# eNode_Spark.net
KiCad netlist of a schematic drawn in EAGLE
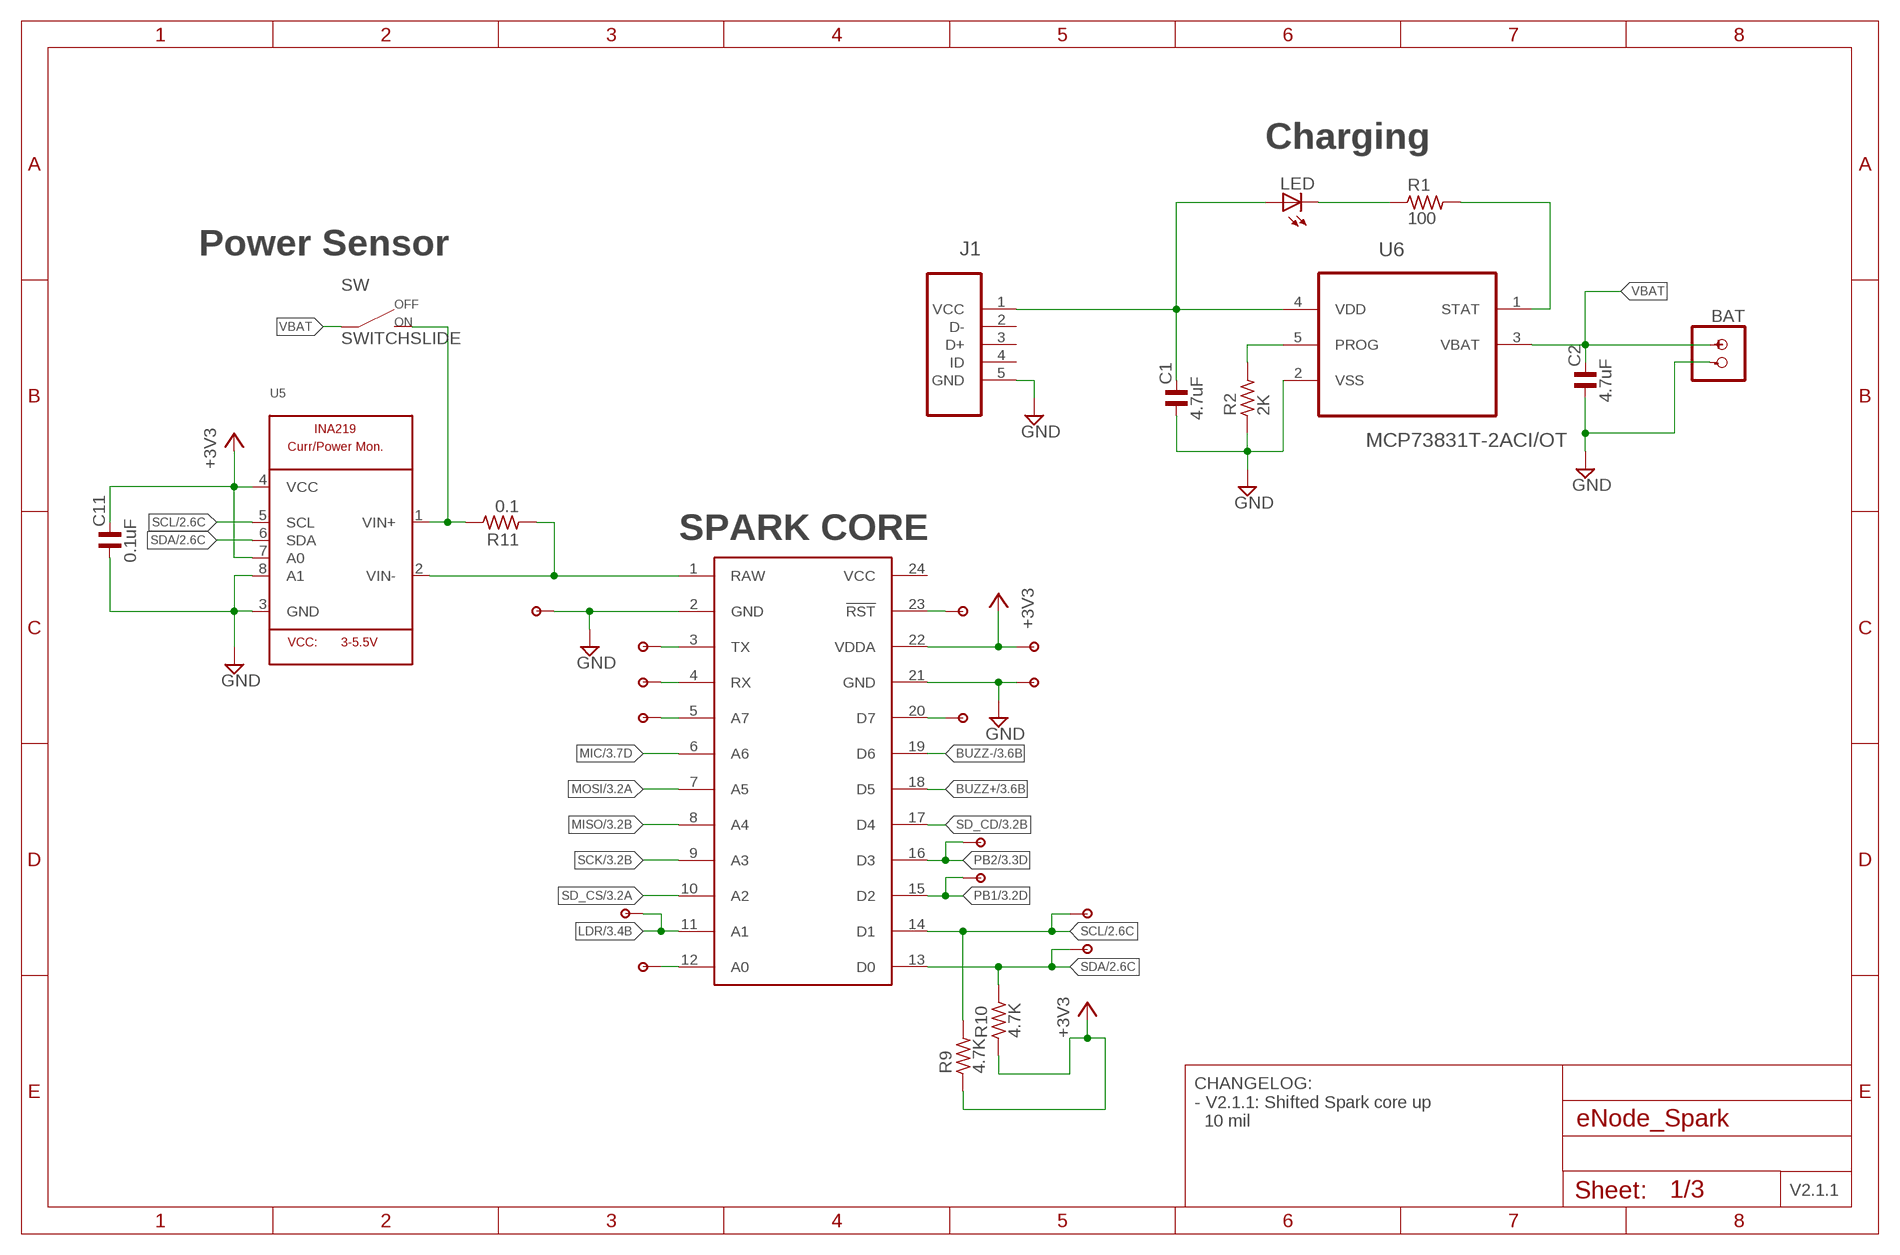
[diagram p0: schematic, sheet 1]
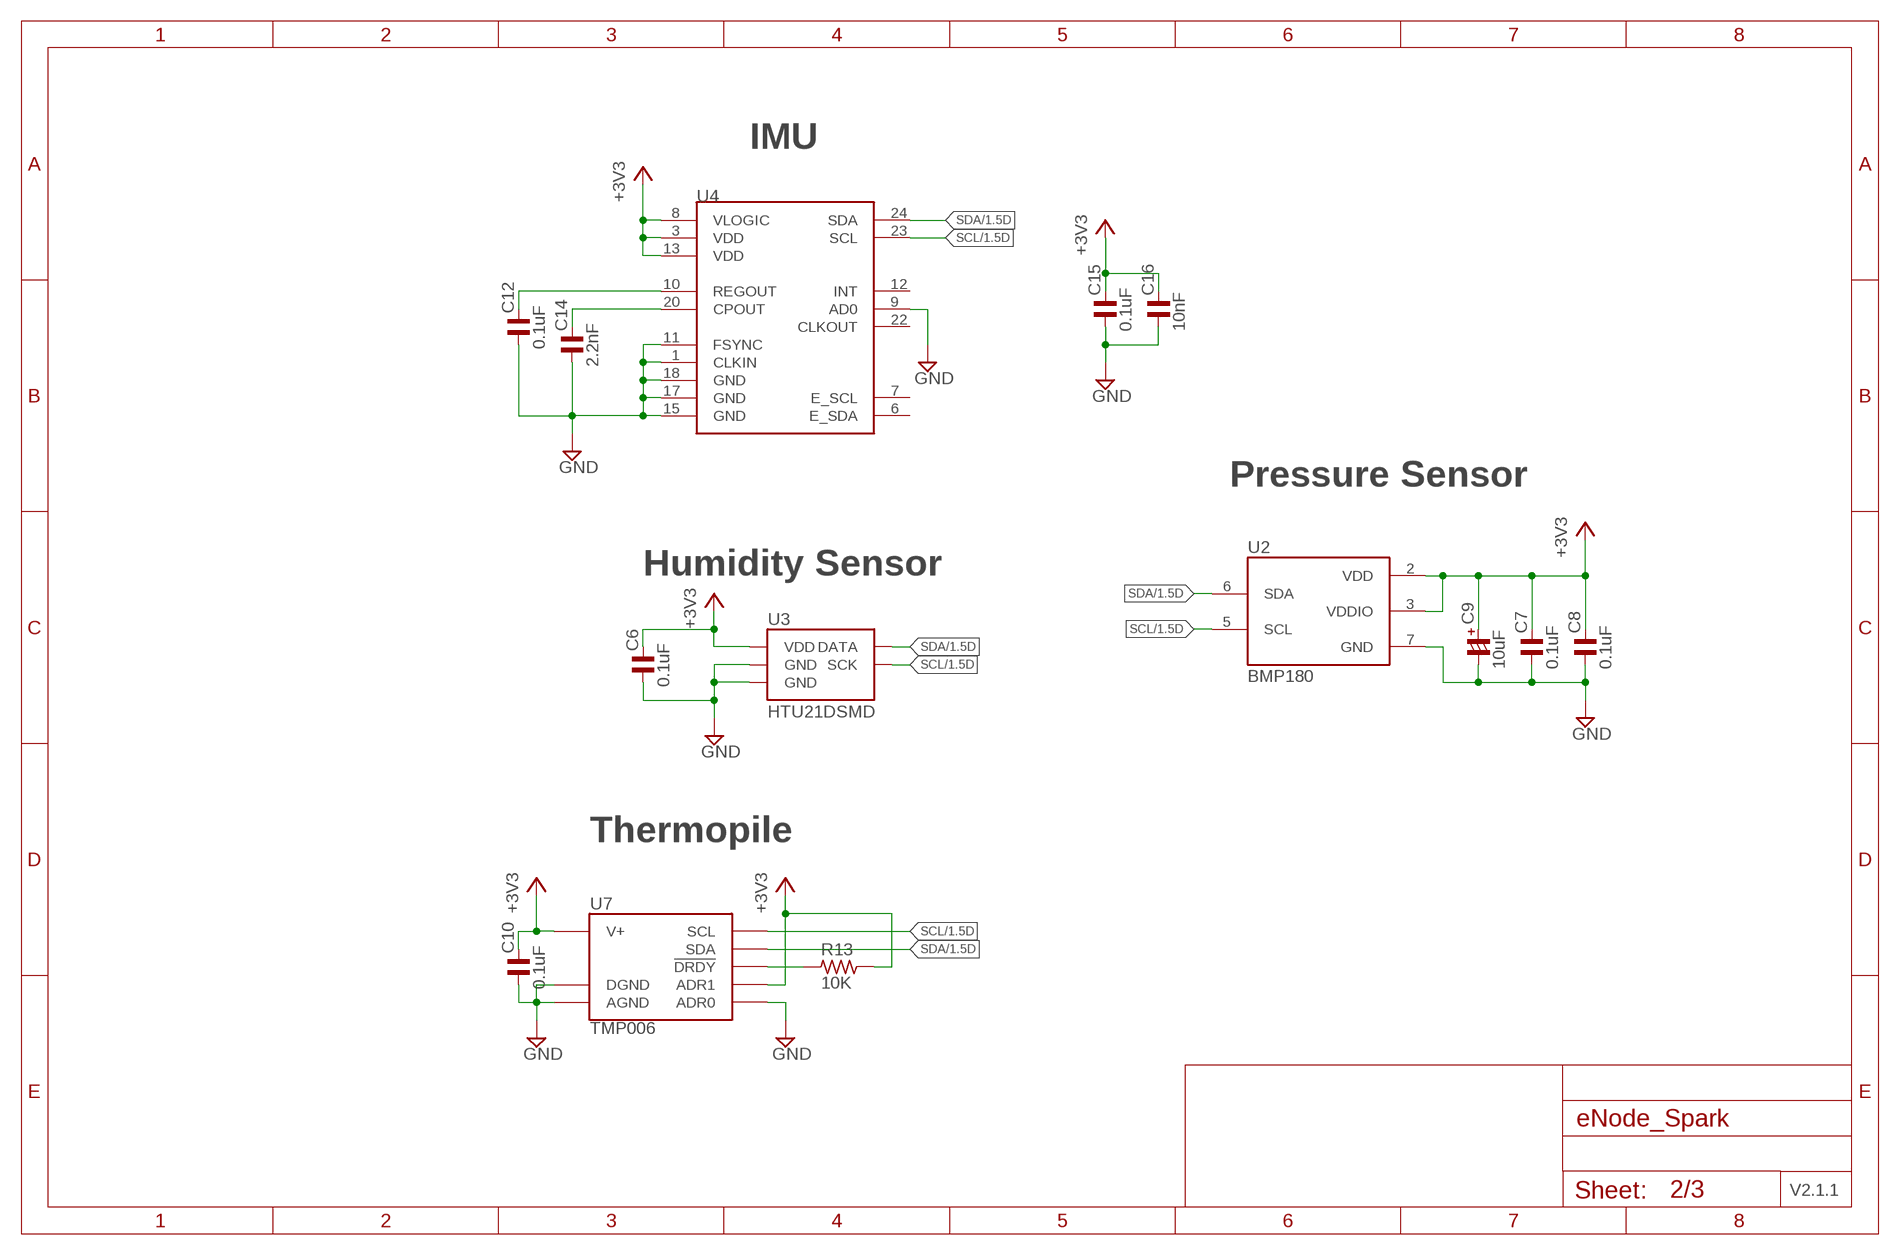
[diagram p1: schematic, sheet 2]
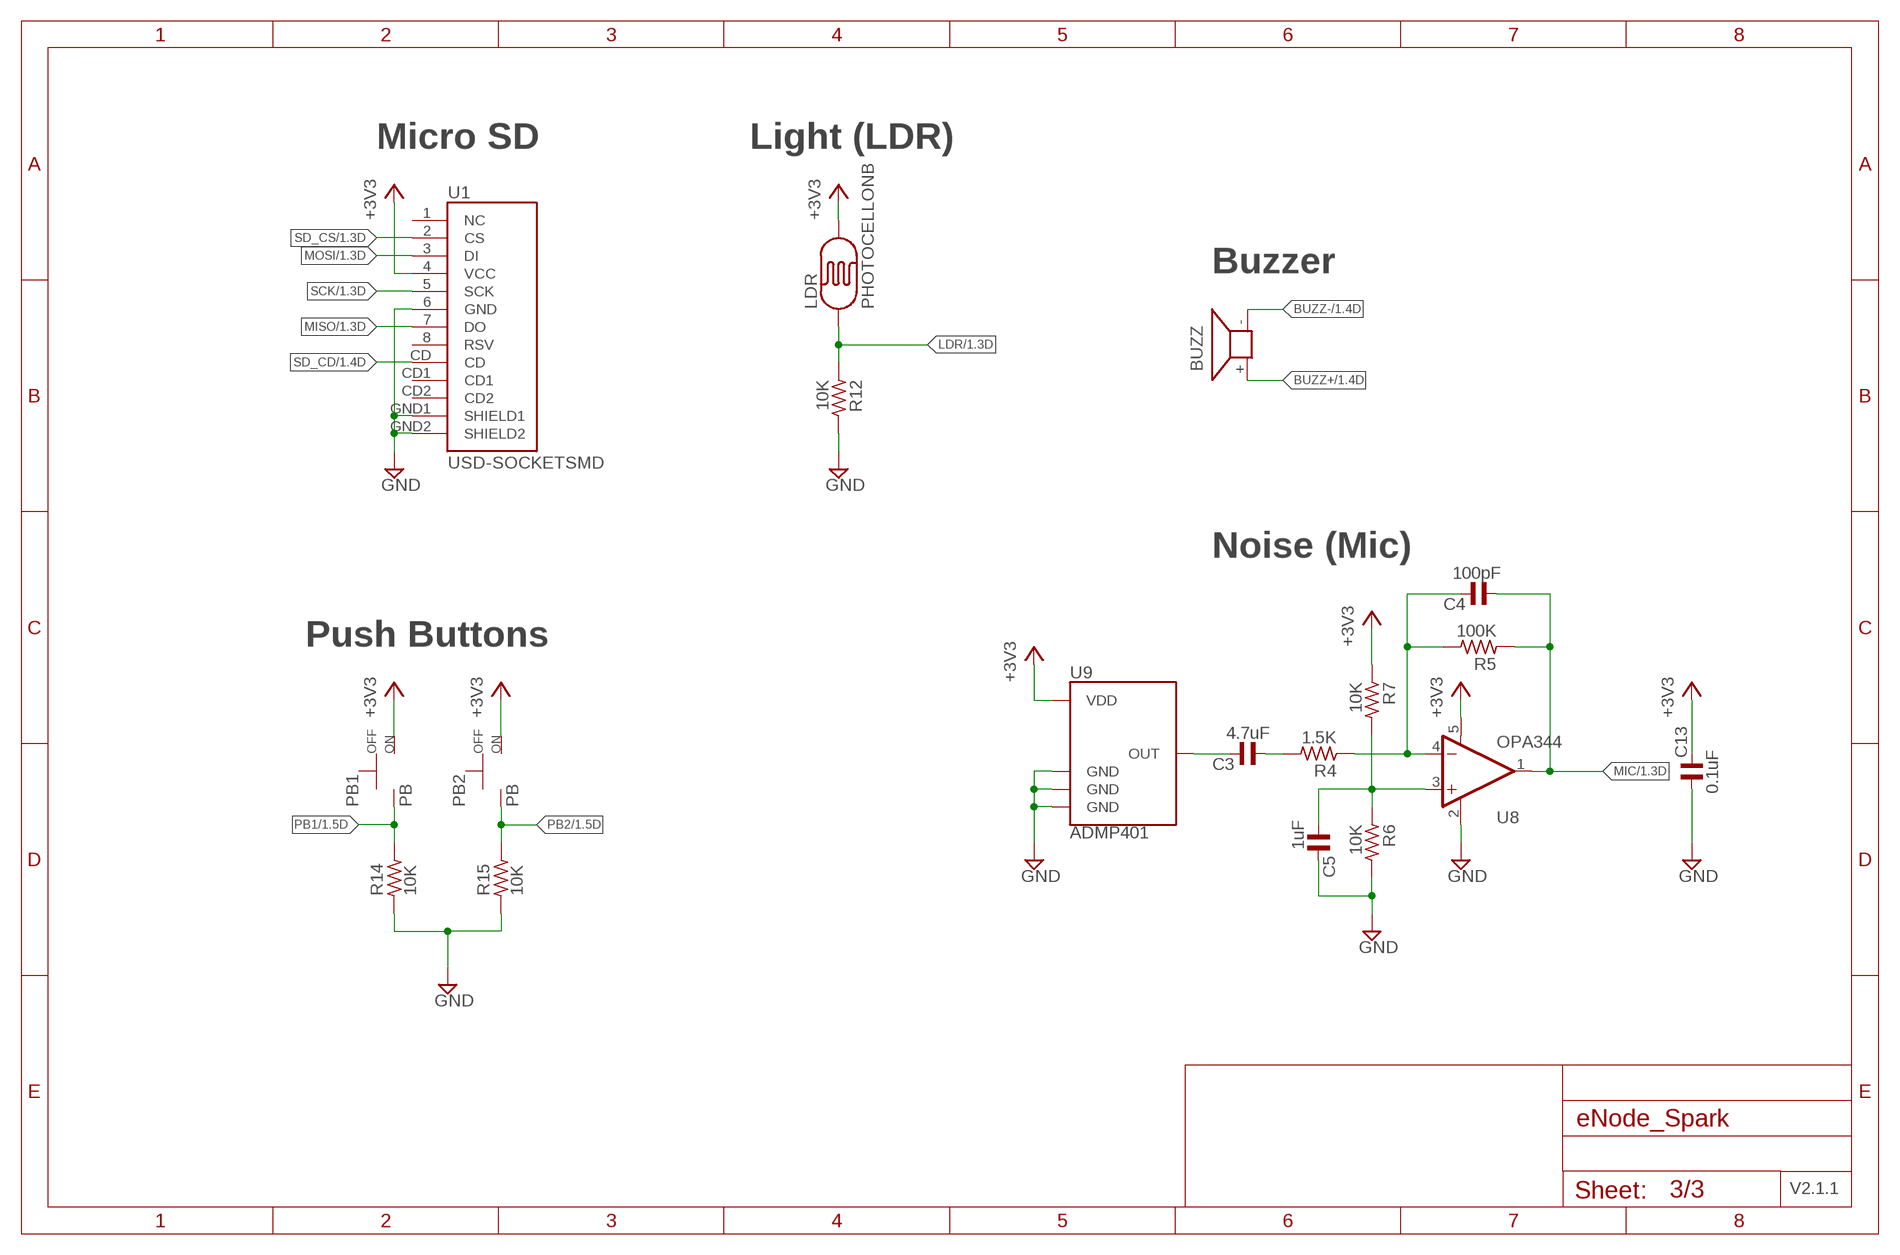
[diagram p2: schematic, sheet 3]

(export (version "E")
  (design (tool "Eeschema 10.0.6"))
  (components
    (comp (ref "BAT")
      (value "BATTERYSMT")
      (footprint "eagle-import:JST-2-SMD")
      (libsource (lib "eagle-import") (part "BATTERYSMT"))
    )
    (comp (ref "C1")
      (value "4.7uF")
      (footprint "eagle-import:C0402")
      (libsource (lib "eagle-import") (part "C_0402"))
    )
    (comp (ref "C2")
      (value "4.7uF")
      (footprint "eagle-import:C0402")
      (libsource (lib "eagle-import") (part "C_0402"))
    )
    (comp (ref "C11")
      (value "0.1uF")
      (footprint "eagle-import:C0402")
      (libsource (lib "eagle-import") (part "C_0402"))
    )
    (comp (ref "J1")
      (value "47346-0001")
      (footprint "eagle-import:MOLEX_47346-0001")
      (libsource (lib "eagle-import") (part "47346-0001"))
    )
    (comp (ref "LED")
      (value "LED")
      (footprint "eagle-import:RA_SMD_LED")
      (libsource (lib "eagle-import") (part "LED"))
    )
    (comp (ref "R1")
      (value "100")
      (footprint "eagle-import:R0603")
      (libsource (lib "eagle-import") (part "R_0603"))
    )
    (comp (ref "R2")
      (value "2K")
      (footprint "eagle-import:R0603")
      (libsource (lib "eagle-import") (part "R_0603"))
    )
    (comp (ref "R9")
      (value "4.7K")
      (footprint "eagle-import:R0603")
      (libsource (lib "eagle-import") (part "R_0603"))
    )
    (comp (ref "R10")
      (value "4.7K")
      (footprint "eagle-import:R0603")
      (libsource (lib "eagle-import") (part "R_0603"))
    )
    (comp (ref "R11")
      (value "0.1")
      (footprint "eagle-import:R2512")
      (libsource (lib "eagle-import") (part "R_2512"))
    )
    (comp (ref "SPARK")
      (value "SPARK_CORECORE")
      (footprint "eagle-import:SPARK_CORE")
      (libsource (lib "eagle-import") (part "SPARK_CORECORE"))
    )
    (comp (ref "SW")
      (value "SWITCHSLIDE")
      (footprint "eagle-import:CHANGE_OVER_SLIDE")
      (libsource (lib "eagle-import") (part "SWITCHSLIDE"))
    )
    (comp (ref "U$1")
      (value "1PIN")
      (footprint "eagle-import:1PIN")
      (libsource (lib "eagle-import") (part "1PIN"))
    )
    (comp (ref "U$2")
      (value "1PIN")
      (footprint "eagle-import:1PIN")
      (libsource (lib "eagle-import") (part "1PIN"))
    )
    (comp (ref "U$6")
      (value "1PIN")
      (footprint "eagle-import:1PIN")
      (libsource (lib "eagle-import") (part "1PIN"))
    )
    (comp (ref "U$7")
      (value "1PIN")
      (footprint "eagle-import:1PIN")
      (libsource (lib "eagle-import") (part "1PIN"))
    )
    (comp (ref "U$8")
      (value "1PIN")
      (footprint "eagle-import:1PIN")
      (libsource (lib "eagle-import") (part "1PIN"))
    )
    (comp (ref "U$9")
      (value "1PIN")
      (footprint "eagle-import:1PIN")
      (libsource (lib "eagle-import") (part "1PIN"))
    )
    (comp (ref "U$10")
      (value "1PIN")
      (footprint "eagle-import:1PIN")
      (libsource (lib "eagle-import") (part "1PIN"))
    )
    (comp (ref "U$11")
      (value "1PIN")
      (footprint "eagle-import:1PIN")
      (libsource (lib "eagle-import") (part "1PIN"))
    )
    (comp (ref "U$12")
      (value "1PIN")
      (footprint "eagle-import:1PIN")
      (libsource (lib "eagle-import") (part "1PIN"))
    )
    (comp (ref "U$13")
      (value "1PIN")
      (footprint "eagle-import:1PIN")
      (libsource (lib "eagle-import") (part "1PIN"))
    )
    (comp (ref "U$14")
      (value "1PIN")
      (footprint "eagle-import:1PIN")
      (libsource (lib "eagle-import") (part "1PIN"))
    )
    (comp (ref "U$15")
      (value "1PIN")
      (footprint "eagle-import:1PIN")
      (libsource (lib "eagle-import") (part "1PIN"))
    )
    (comp (ref "U$16")
      (value "1PIN")
      (footprint "eagle-import:1PIN")
      (libsource (lib "eagle-import") (part "1PIN"))
    )
    (comp (ref "U$17")
      (value "1PIN")
      (footprint "eagle-import:1PIN")
      (libsource (lib "eagle-import") (part "1PIN"))
    )
    (comp (ref "U5")
      (value "INA219")
      (footprint "eagle-import:SOT23-8")
      (libsource (lib "eagle-import") (part "INA219"))
    )
    (comp (ref "U6")
      (value "MCP73831T-2ACI/OT")
      (footprint "eagle-import:SOT95P280X145-5N")
      (libsource (lib "eagle-import") (part "MCP73831T-2ACI/OT"))
    )
    (comp (ref "C6")
      (value "0.1uF")
      (footprint "eagle-import:C0402")
      (libsource (lib "eagle-import") (part "C_0402"))
    )
    (comp (ref "C7")
      (value "0.1uF")
      (footprint "eagle-import:C0402")
      (libsource (lib "eagle-import") (part "C_0402"))
    )
    (comp (ref "C8")
      (value "0.1uF")
      (footprint "eagle-import:C0402")
      (libsource (lib "eagle-import") (part "C_0402"))
    )
    (comp (ref "C9")
      (value "10uF")
      (footprint "eagle-import:C1206_T")
      (libsource (lib "eagle-import") (part "CP_1206/T"))
    )
    (comp (ref "C10")
      (value "0.1uF")
      (footprint "eagle-import:C0402")
      (libsource (lib "eagle-import") (part "C_0402"))
    )
    (comp (ref "C12")
      (value "0.1uF")
      (footprint "eagle-import:C0402")
      (libsource (lib "eagle-import") (part "C_0402"))
    )
    (comp (ref "C14")
      (value "2.2nF")
      (footprint "eagle-import:C0402")
      (libsource (lib "eagle-import") (part "C_0402"))
    )
    (comp (ref "C15")
      (value "0.1uF")
      (footprint "eagle-import:C0402")
      (libsource (lib "eagle-import") (part "C_0402"))
    )
    (comp (ref "C16")
      (value "10nF")
      (footprint "eagle-import:C0402")
      (libsource (lib "eagle-import") (part "C_0402"))
    )
    (comp (ref "R13")
      (value "10K")
      (footprint "eagle-import:R0603")
      (libsource (lib "eagle-import") (part "R_0603"))
    )
    (comp (ref "U2")
      (value "BMP180")
      (footprint "eagle-import:BMP180")
      (libsource (lib "eagle-import") (part "BMP180"))
    )
    (comp (ref "U3")
      (value "HTU21DSMD")
      (footprint "eagle-import:HTU21D")
      (libsource (lib "eagle-import") (part "HTU21DSMD"))
    )
    (comp (ref "U4")
      (value "MPU-9150QFN-24-NP")
      (footprint "eagle-import:QFN-24-NP")
      (libsource (lib "eagle-import") (part "MPU-9150QFN-24-NP"))
    )
    (comp (ref "U7")
      (value "TMP006")
      (footprint "eagle-import:BGA8DS")
      (libsource (lib "eagle-import") (part "TMP006"))
    )
    (comp (ref "BUZZ")
      (value "BUZZER")
      (footprint "eagle-import:OFFBOARD_NOSIGN")
      (libsource (lib "eagle-import") (part "BUZZER"))
    )
    (comp (ref "C3")
      (value "4.7uF")
      (footprint "eagle-import:C0402")
      (libsource (lib "eagle-import") (part "C_0402"))
    )
    (comp (ref "C4")
      (value "100pF")
      (footprint "eagle-import:C0402")
      (libsource (lib "eagle-import") (part "C_0402"))
    )
    (comp (ref "C5")
      (value "1uF")
      (footprint "eagle-import:C0402")
      (libsource (lib "eagle-import") (part "C_0402"))
    )
    (comp (ref "C13")
      (value "0.1uF")
      (footprint "eagle-import:C0402")
      (libsource (lib "eagle-import") (part "C_0402"))
    )
    (comp (ref "LDR")
      (value "PHOTOCELLONB")
      (footprint "eagle-import:ON_BOARD")
      (libsource (lib "eagle-import") (part "PHOTOCELLONB"))
    )
    (comp (ref "PB1") (value "PB") (footprint "eagle-import:PB") (libsource (lib "eagle-import") (part "PB")))
    (comp (ref "PB2") (value "PB") (footprint "eagle-import:PB") (libsource (lib "eagle-import") (part "PB")))
    (comp (ref "R4")
      (value "1.5K")
      (footprint "eagle-import:R0402")
      (libsource (lib "eagle-import") (part "R_0402"))
    )
    (comp (ref "R5")
      (value "100K")
      (footprint "eagle-import:R0402")
      (libsource (lib "eagle-import") (part "R_0402"))
    )
    (comp (ref "R6")
      (value "10K")
      (footprint "eagle-import:R0402")
      (libsource (lib "eagle-import") (part "R_0402"))
    )
    (comp (ref "R7")
      (value "10K")
      (footprint "eagle-import:R0402")
      (libsource (lib "eagle-import") (part "R_0402"))
    )
    (comp (ref "R12")
      (value "10K")
      (footprint "eagle-import:R0603")
      (libsource (lib "eagle-import") (part "R_0603"))
    )
    (comp (ref "R14")
      (value "10K")
      (footprint "eagle-import:R0603")
      (libsource (lib "eagle-import") (part "R_0603"))
    )
    (comp (ref "R15")
      (value "10K")
      (footprint "eagle-import:R0603")
      (libsource (lib "eagle-import") (part "R_0603"))
    )
    (comp (ref "U1")
      (value "USD-SOCKETSMD")
      (footprint "eagle-import:MICRO-SD-SOCKET-PP")
      (libsource (lib "eagle-import") (part "USD-SOCKETSMD"))
    )
    (comp (ref "U8")
      (value "OPA344")
      (footprint "eagle-import:SOT23-5")
      (libsource (lib "eagle-import") (part "OPA344"))
    )
    (comp (ref "U9")
      (value "ADMP401")
      (footprint "eagle-import:ADMP401")
      (libsource (lib "eagle-import") (part "ADMP401"))
    )
  )
  (nets
    (net (code "1") (name "+3V3") (class "Default")
      (node (ref "C10") (pin "2") (pinfunction "2_2") (pintype "passive"))
      (node (ref "C11") (pin "2") (pinfunction "2_2") (pintype "passive"))
      (node (ref "C13") (pin "2") (pinfunction "2_2") (pintype "passive"))
      (node (ref "C15") (pin "2") (pinfunction "2_2") (pintype "passive"))
      (node (ref "C16") (pin "2") (pinfunction "2_2") (pintype "passive"))
      (node (ref "C6") (pin "2") (pinfunction "2_2") (pintype "passive"))
      (node (ref "C7") (pin "2") (pinfunction "2_2") (pintype "passive"))
      (node (ref "C8") (pin "2") (pinfunction "2_2") (pintype "passive"))
      (node (ref "C9") (pin "+") (pinfunction "+_+") (pintype "passive"))
      (node (ref "LDR") (pin "2") (pinfunction "P$2_2") (pintype "bidirectional"))
      (node (ref "PB1") (pin "2") (pinfunction "2_2") (pintype "bidirectional"))
      (node (ref "PB2") (pin "2") (pinfunction "2_2") (pintype "bidirectional"))
      (node (ref "R10") (pin "1") (pinfunction "1_1") (pintype "passive"))
      (node (ref "R13") (pin "2") (pinfunction "2_2") (pintype "passive"))
      (node (ref "R7") (pin "1") (pinfunction "1_1") (pintype "passive"))
      (node (ref "R9") (pin "1") (pinfunction "1_1") (pintype "passive"))
      (node (ref "SPARK") (pin "22") (pinfunction "VDDA_22") (pintype "power_in"))
      (node (ref "U$6") (pin "P$1") (pinfunction "P$1_P$1") (pintype "bidirectional"))
      (node (ref "U1") (pin "4") (pinfunction "VCC_4") (pintype "bidirectional"))
      (node (ref "U2") (pin "2") (pinfunction "VDD_2") (pintype "power_in"))
      (node (ref "U2") (pin "3") (pinfunction "VDDIO_3") (pintype "power_in"))
      (node (ref "U3") (pin "VDD") (pinfunction "VDD_VDD") (pintype "power_in"))
      (node (ref "U4") (pin "13") (pinfunction "VDD_13") (pintype "bidirectional"))
      (node (ref "U4") (pin "3") (pinfunction "VDD_3") (pintype "bidirectional"))
      (node (ref "U4") (pin "8") (pinfunction "VLOGIC_8") (pintype "bidirectional"))
      (node (ref "U5") (pin "4") (pinfunction "VCC_4") (pintype "bidirectional"))
      (node (ref "U5") (pin "7") (pinfunction "A0_7") (pintype "bidirectional"))
      (node (ref "U7") (pin "A3") (pinfunction "V+_A3") (pintype "bidirectional"))
      (node (ref "U7") (pin "B1") (pinfunction "ADR1_B1") (pintype "bidirectional"))
      (node (ref "U8") (pin "5") (pinfunction "V+_5") (pintype "power_in"))
      (node (ref "U9") (pin "5") (pinfunction "VDD_5") (pintype "bidirectional"))
    )
    (net (code "2") (name "BUZZ+") (class "Default")
      (node (ref "BUZZ") (pin "+") (pinfunction "+_+") (pintype "passive"))
      (node (ref "SPARK") (pin "18") (pinfunction "D5_18") (pintype "bidirectional"))
    )
    (net (code "3") (name "BUZZ-") (class "Default")
      (node (ref "BUZZ") (pin "-") (pinfunction "-_-") (pintype "passive"))
      (node (ref "SPARK") (pin "19") (pinfunction "D6_19") (pintype "bidirectional"))
    )
    (net (code "4") (name "GND") (class "Default")
      (node (ref "BAT") (pin "-") (pinfunction "-_-") (pintype "passive"))
      (node (ref "C1") (pin "1") (pinfunction "1_1") (pintype "passive"))
      (node (ref "C10") (pin "1") (pinfunction "1_1") (pintype "passive"))
      (node (ref "C11") (pin "1") (pinfunction "1_1") (pintype "passive"))
      (node (ref "C12") (pin "1") (pinfunction "1_1") (pintype "passive"))
      (node (ref "C13") (pin "1") (pinfunction "1_1") (pintype "passive"))
      (node (ref "C14") (pin "1") (pinfunction "1_1") (pintype "passive"))
      (node (ref "C15") (pin "1") (pinfunction "1_1") (pintype "passive"))
      (node (ref "C16") (pin "1") (pinfunction "1_1") (pintype "passive"))
      (node (ref "C2") (pin "1") (pinfunction "1_1") (pintype "passive"))
      (node (ref "C5") (pin "2") (pinfunction "2_2") (pintype "passive"))
      (node (ref "C6") (pin "1") (pinfunction "1_1") (pintype "passive"))
      (node (ref "C7") (pin "1") (pinfunction "1_1") (pintype "passive"))
      (node (ref "C8") (pin "1") (pinfunction "1_1") (pintype "passive"))
      (node (ref "C9") (pin "-") (pinfunction "-_-") (pintype "passive"))
      (node (ref "J1") (pin "5") (pinfunction "GND_5") (pintype "input"))
      (node (ref "R12") (pin "2") (pinfunction "2_2") (pintype "passive"))
      (node (ref "R14") (pin "1") (pinfunction "1_1") (pintype "passive"))
      (node (ref "R15") (pin "1") (pinfunction "1_1") (pintype "passive"))
      (node (ref "R2") (pin "1") (pinfunction "1_1") (pintype "passive"))
      (node (ref "R6") (pin "2") (pinfunction "2_2") (pintype "passive"))
      (node (ref "SPARK") (pin "2") (pinfunction "GND_2") (pintype "power_in"))
      (node (ref "SPARK") (pin "21") (pinfunction "GND_21") (pintype "power_in"))
      (node (ref "U$11") (pin "P$1") (pinfunction "P$1_P$1") (pintype "bidirectional"))
      (node (ref "U$17") (pin "P$1") (pinfunction "P$1_P$1") (pintype "bidirectional"))
      (node (ref "U1") (pin "6") (pinfunction "GND_6") (pintype "bidirectional"))
      (node (ref "U1") (pin "GND1") (pinfunction "SHIELD1_GND1") (pintype "bidirectional"))
      (node (ref "U1") (pin "GND2") (pinfunction "SHIELD2_GND2") (pintype "bidirectional"))
      (node (ref "U2") (pin "7") (pinfunction "GND_7") (pintype "power_in"))
      (node (ref "U3") (pin "7") (pinfunction "GND_7") (pintype "power_in"))
      (node (ref "U3") (pin "GND") (pinfunction "GND_GND") (pintype "power_in"))
      (node (ref "U4") (pin "1") (pinfunction "CLKIN_1") (pintype "bidirectional"))
      (node (ref "U4") (pin "11") (pinfunction "FSYNC_11") (pintype "bidirectional"))
      (node (ref "U4") (pin "15") (pinfunction "GND_15") (pintype "bidirectional"))
      (node (ref "U4") (pin "17") (pinfunction "GND_17") (pintype "bidirectional"))
      (node (ref "U4") (pin "18") (pinfunction "GND_18") (pintype "bidirectional"))
      (node (ref "U4") (pin "9") (pinfunction "AD0_9") (pintype "bidirectional"))
      (node (ref "U5") (pin "3") (pinfunction "GND_3") (pintype "bidirectional"))
      (node (ref "U5") (pin "8") (pinfunction "A1_8") (pintype "bidirectional"))
      (node (ref "U6") (pin "2") (pinfunction "VSS_2") (pintype "power_in"))
      (node (ref "U7") (pin "A1") (pinfunction "DGND_A1") (pintype "bidirectional"))
      (node (ref "U7") (pin "A2") (pinfunction "AGND_A2") (pintype "bidirectional"))
      (node (ref "U7") (pin "C1") (pinfunction "ADR0_C1") (pintype "bidirectional"))
      (node (ref "U8") (pin "2") (pinfunction "V-_2") (pintype "power_in"))
      (node (ref "U9") (pin "2") (pinfunction "GND_2") (pintype "bidirectional"))
      (node (ref "U9") (pin "4") (pinfunction "GND_4") (pintype "bidirectional"))
      (node (ref "U9") (pin "6") (pinfunction "GND_6") (pintype "bidirectional"))
    )
    (net (code "5") (name "LDR") (class "Default")
      (node (ref "LDR") (pin "1") (pinfunction "P$1_1") (pintype "bidirectional"))
      (node (ref "R12") (pin "1") (pinfunction "1_1") (pintype "passive"))
      (node (ref "SPARK") (pin "11") (pinfunction "A1_11") (pintype "bidirectional"))
      (node (ref "U$16") (pin "P$1") (pinfunction "P$1_P$1") (pintype "bidirectional"))
    )
    (net (code "6") (name "MIC") (class "Default")
      (node (ref "C4") (pin "1") (pinfunction "1_1") (pintype "passive"))
      (node (ref "R5") (pin "1") (pinfunction "1_1") (pintype "passive"))
      (node (ref "SPARK") (pin "6") (pinfunction "A6_6") (pintype "bidirectional"))
      (node (ref "U8") (pin "1") (pinfunction "OUT_1") (pintype "output"))
    )
    (net (code "7") (name "MISO") (class "Default")
      (node (ref "SPARK") (pin "8") (pinfunction "A4_8") (pintype "bidirectional"))
      (node (ref "U1") (pin "7") (pinfunction "DO_7") (pintype "bidirectional"))
    )
    (net (code "8") (name "MOSI") (class "Default")
      (node (ref "SPARK") (pin "7") (pinfunction "A5_7") (pintype "bidirectional"))
      (node (ref "U1") (pin "3") (pinfunction "DI_3") (pintype "bidirectional"))
    )
    (net (code "9") (name "Net-(C3-Pad1)") (class "Default")
      (node (ref "C3") (pin "1") (pinfunction "1_1") (pintype "passive"))
      (node (ref "R4") (pin "2") (pinfunction "2_2") (pintype "passive"))
    )
    (net (code "10") (name "Net-(J1-VCC)") (class "Default")
      (node (ref "C1") (pin "2") (pinfunction "2_2") (pintype "passive"))
      (node (ref "J1") (pin "1") (pinfunction "VCC_1") (pintype "input"))
      (node (ref "LED") (pin "A") (pinfunction "A_A") (pintype "passive"))
      (node (ref "U6") (pin "4") (pinfunction "VDD_4") (pintype "power_in"))
    )
    (net (code "11") (name "Net-(LED-PadC)") (class "Default")
      (node (ref "LED") (pin "C") (pinfunction "C_C") (pintype "passive"))
      (node (ref "R1") (pin "1") (pinfunction "1_1") (pintype "passive"))
    )
    (net (code "12") (name "Net-(SPARK-A0)") (class "Default")
      (node (ref "SPARK") (pin "12") (pinfunction "A0_12") (pintype "bidirectional"))
      (node (ref "U$1") (pin "P$1") (pinfunction "P$1_P$1") (pintype "bidirectional"))
    )
    (net (code "13") (name "Net-(SPARK-A7)") (class "Default")
      (node (ref "SPARK") (pin "5") (pinfunction "A7_5") (pintype "bidirectional"))
      (node (ref "U$2") (pin "P$1") (pinfunction "P$1_P$1") (pintype "bidirectional"))
    )
    (net (code "14") (name "Net-(SPARK-D7)") (class "Default")
      (node (ref "SPARK") (pin "20") (pinfunction "D7_20") (pintype "bidirectional"))
      (node (ref "U$10") (pin "P$1") (pinfunction "P$1_P$1") (pintype "bidirectional"))
    )
    (net (code "15") (name "Net-(SPARK-RAW)") (class "Default")
      (node (ref "R11") (pin "1") (pinfunction "1_1") (pintype "passive"))
      (node (ref "SPARK") (pin "1") (pinfunction "RAW_1") (pintype "power_in"))
      (node (ref "U5") (pin "2") (pinfunction "VIN-_2") (pintype "bidirectional"))
    )
    (net (code "16") (name "Net-(SPARK-RX)") (class "Default")
      (node (ref "SPARK") (pin "4") (pinfunction "RX_4") (pintype "bidirectional"))
      (node (ref "U$13") (pin "P$1") (pinfunction "P$1_P$1") (pintype "bidirectional"))
    )
    (net (code "17") (name "Net-(SPARK-TX)") (class "Default")
      (node (ref "SPARK") (pin "3") (pinfunction "TX_3") (pintype "bidirectional"))
      (node (ref "U$12") (pin "P$1") (pinfunction "P$1_P$1") (pintype "bidirectional"))
    )
    (net (code "18") (name "Net-(SPARK-~{RST})") (class "Default")
      (node (ref "SPARK") (pin "23") (pinfunction "~{RST}_23") (pintype "bidirectional"))
      (node (ref "U$14") (pin "P$1") (pinfunction "P$1_P$1") (pintype "bidirectional"))
    )
    (net (code "19") (name "Net-(U4-CPOUT)") (class "Default")
      (node (ref "C14") (pin "2") (pinfunction "2_2") (pintype "passive"))
      (node (ref "U4") (pin "20") (pinfunction "CPOUT_20") (pintype "bidirectional"))
    )
    (net (code "20") (name "Net-(U4-REGOUT)") (class "Default")
      (node (ref "C12") (pin "2") (pinfunction "2_2") (pintype "passive"))
      (node (ref "U4") (pin "10") (pinfunction "REGOUT_10") (pintype "bidirectional"))
    )
    (net (code "21") (name "Net-(U5-VIN+)") (class "Default")
      (node (ref "R11") (pin "2") (pinfunction "2_2") (pintype "passive"))
      (node (ref "SW") (pin "2") (pinfunction "2_2") (pintype "bidirectional"))
      (node (ref "U5") (pin "1") (pinfunction "VIN+_1") (pintype "bidirectional"))
    )
    (net (code "22") (name "Net-(U6-PROG)") (class "Default")
      (node (ref "R2") (pin "2") (pinfunction "2_2") (pintype "passive"))
      (node (ref "U6") (pin "5") (pinfunction "PROG_5") (pintype "input"))
    )
    (net (code "23") (name "Net-(U6-STAT)") (class "Default")
      (node (ref "R1") (pin "2") (pinfunction "2_2") (pintype "passive"))
      (node (ref "U6") (pin "1") (pinfunction "STAT_1") (pintype "output"))
    )
    (net (code "24") (name "Net-(U7-~{DRDY})") (class "Default")
      (node (ref "R13") (pin "1") (pinfunction "1_1") (pintype "passive"))
      (node (ref "U7") (pin "C2") (pinfunction "~{DRDY}_C2") (pintype "bidirectional"))
    )
    (net (code "25") (name "Net-(U8-+IN)") (class "Default")
      (node (ref "C5") (pin "1") (pinfunction "1_1") (pintype "passive"))
      (node (ref "R6") (pin "1") (pinfunction "1_1") (pintype "passive"))
      (node (ref "R7") (pin "2") (pinfunction "2_2") (pintype "passive"))
      (node (ref "U8") (pin "3") (pinfunction "+IN_3") (pintype "input"))
    )
    (net (code "26") (name "Net-(U8--IN)") (class "Default")
      (node (ref "C4") (pin "2") (pinfunction "2_2") (pintype "passive"))
      (node (ref "R4") (pin "1") (pinfunction "1_1") (pintype "passive"))
      (node (ref "R5") (pin "2") (pinfunction "2_2") (pintype "passive"))
      (node (ref "U8") (pin "4") (pinfunction "-IN_4") (pintype "input"))
    )
    (net (code "27") (name "Net-(U9-OUT)") (class "Default")
      (node (ref "C3") (pin "2") (pinfunction "2_2") (pintype "passive"))
      (node (ref "U9") (pin "1") (pinfunction "OUT_1") (pintype "bidirectional"))
    )
    (net (code "28") (name "PB1") (class "Default")
      (node (ref "PB1") (pin "1") (pinfunction "1_1") (pintype "bidirectional"))
      (node (ref "R14") (pin "2") (pinfunction "2_2") (pintype "passive"))
      (node (ref "SPARK") (pin "15") (pinfunction "D2_15") (pintype "bidirectional"))
      (node (ref "U$9") (pin "P$1") (pinfunction "P$1_P$1") (pintype "bidirectional"))
    )
    (net (code "29") (name "PB2") (class "Default")
      (node (ref "PB2") (pin "1") (pinfunction "1_1") (pintype "bidirectional"))
      (node (ref "R15") (pin "2") (pinfunction "2_2") (pintype "passive"))
      (node (ref "SPARK") (pin "16") (pinfunction "D3_16") (pintype "bidirectional"))
      (node (ref "U$15") (pin "P$1") (pinfunction "P$1_P$1") (pintype "bidirectional"))
    )
    (net (code "30") (name "SCK") (class "Default")
      (node (ref "SPARK") (pin "9") (pinfunction "A3_9") (pintype "bidirectional"))
      (node (ref "U1") (pin "5") (pinfunction "SCK_5") (pintype "bidirectional"))
    )
    (net (code "31") (name "SCL") (class "Default")
      (node (ref "R9") (pin "2") (pinfunction "2_2") (pintype "passive"))
      (node (ref "SPARK") (pin "14") (pinfunction "D1_14") (pintype "bidirectional"))
      (node (ref "U$7") (pin "P$1") (pinfunction "P$1_P$1") (pintype "bidirectional"))
      (node (ref "U2") (pin "5") (pinfunction "SCL_5") (pintype "input"))
      (node (ref "U3") (pin "SCK") (pinfunction "SCK_SCK") (pintype "input"))
      (node (ref "U4") (pin "23") (pinfunction "SCL_23") (pintype "bidirectional"))
      (node (ref "U5") (pin "5") (pinfunction "SCL_5") (pintype "bidirectional"))
      (node (ref "U7") (pin "B3") (pinfunction "SCL_B3") (pintype "bidirectional"))
    )
    (net (code "32") (name "SDA") (class "Default")
      (node (ref "R10") (pin "2") (pinfunction "2_2") (pintype "passive"))
      (node (ref "SPARK") (pin "13") (pinfunction "D0_13") (pintype "bidirectional"))
      (node (ref "U$8") (pin "P$1") (pinfunction "P$1_P$1") (pintype "bidirectional"))
      (node (ref "U2") (pin "6") (pinfunction "SDA_6") (pintype "bidirectional"))
      (node (ref "U3") (pin "DATA") (pinfunction "DATA_DATA") (pintype "bidirectional"))
      (node (ref "U4") (pin "24") (pinfunction "SDA_24") (pintype "bidirectional"))
      (node (ref "U5") (pin "6") (pinfunction "SDA_6") (pintype "bidirectional"))
      (node (ref "U7") (pin "C3") (pinfunction "SDA_C3") (pintype "bidirectional"))
    )
    (net (code "33") (name "SD_CD") (class "Default")
      (node (ref "SPARK") (pin "17") (pinfunction "D4_17") (pintype "bidirectional"))
      (node (ref "U1") (pin "CD") (pinfunction "CD_CD") (pintype "bidirectional"))
    )
    (net (code "34") (name "SD_CS") (class "Default")
      (node (ref "SPARK") (pin "10") (pinfunction "A2_10") (pintype "bidirectional"))
      (node (ref "U1") (pin "2") (pinfunction "CS_2") (pintype "bidirectional"))
    )
    (net (code "35") (name "VBAT") (class "Default")
      (node (ref "BAT") (pin "+") (pinfunction "+_+") (pintype "passive"))
      (node (ref "C2") (pin "2") (pinfunction "2_2") (pintype "passive"))
      (node (ref "SW") (pin "1") (pinfunction "1_1") (pintype "bidirectional"))
      (node (ref "U6") (pin "3") (pinfunction "VBAT_3") (pintype "output"))
    )
    (net (code "36") (name "VCC") (class "Default")
      (node (ref "SPARK") (pin "24") (pinfunction "VCC_24") (pintype "power_in"))
    )
    (net (code "37") (name "unconnected-(J1-D+-Pad3)") (class "Default")
      (node (ref "J1") (pin "3") (pinfunction "D+_3") (pintype "input"))
    )
    (net (code "38") (name "unconnected-(J1-D--Pad2)") (class "Default")
      (node (ref "J1") (pin "2") (pinfunction "D-_2") (pintype "input"))
    )
    (net (code "39") (name "unconnected-(J1-ID-Pad4)") (class "Default")
      (node (ref "J1") (pin "4") (pinfunction "ID_4") (pintype "input"))
    )
    (net (code "40") (name "unconnected-(U1-NC-Pad1)") (class "Default")
      (node (ref "U1") (pin "1") (pinfunction "NC_1") (pintype "bidirectional"))
    )
    (net (code "41") (name "unconnected-(U1-PadCD1)") (class "Default")
      (node (ref "U1") (pin "CD1") (pinfunction "CD1_CD1") (pintype "bidirectional"))
    )
    (net (code "42") (name "unconnected-(U1-PadCD2)") (class "Default")
      (node (ref "U1") (pin "CD2") (pinfunction "CD2_CD2") (pintype "bidirectional"))
    )
    (net (code "43") (name "unconnected-(U1-RSV-Pad8)") (class "Default")
      (node (ref "U1") (pin "8") (pinfunction "RSV_8") (pintype "bidirectional"))
    )
    (net (code "44") (name "unconnected-(U4-CLKOUT-Pad22)") (class "Default")
      (node (ref "U4") (pin "22") (pinfunction "CLKOUT_22") (pintype "bidirectional"))
    )
    (net (code "45") (name "unconnected-(U4-E_SCL-Pad7)") (class "Default")
      (node (ref "U4") (pin "7") (pinfunction "E_SCL_7") (pintype "bidirectional"))
    )
    (net (code "46") (name "unconnected-(U4-E_SDA-Pad6)") (class "Default")
      (node (ref "U4") (pin "6") (pinfunction "E_SDA_6") (pintype "bidirectional"))
    )
    (net (code "47") (name "unconnected-(U4-INT-Pad12)") (class "Default")
      (node (ref "U4") (pin "12") (pinfunction "INT_12") (pintype "bidirectional"))
    )
  )
)
